# untitled.net
KiCad netlist of a schematic drawn in EAGLE
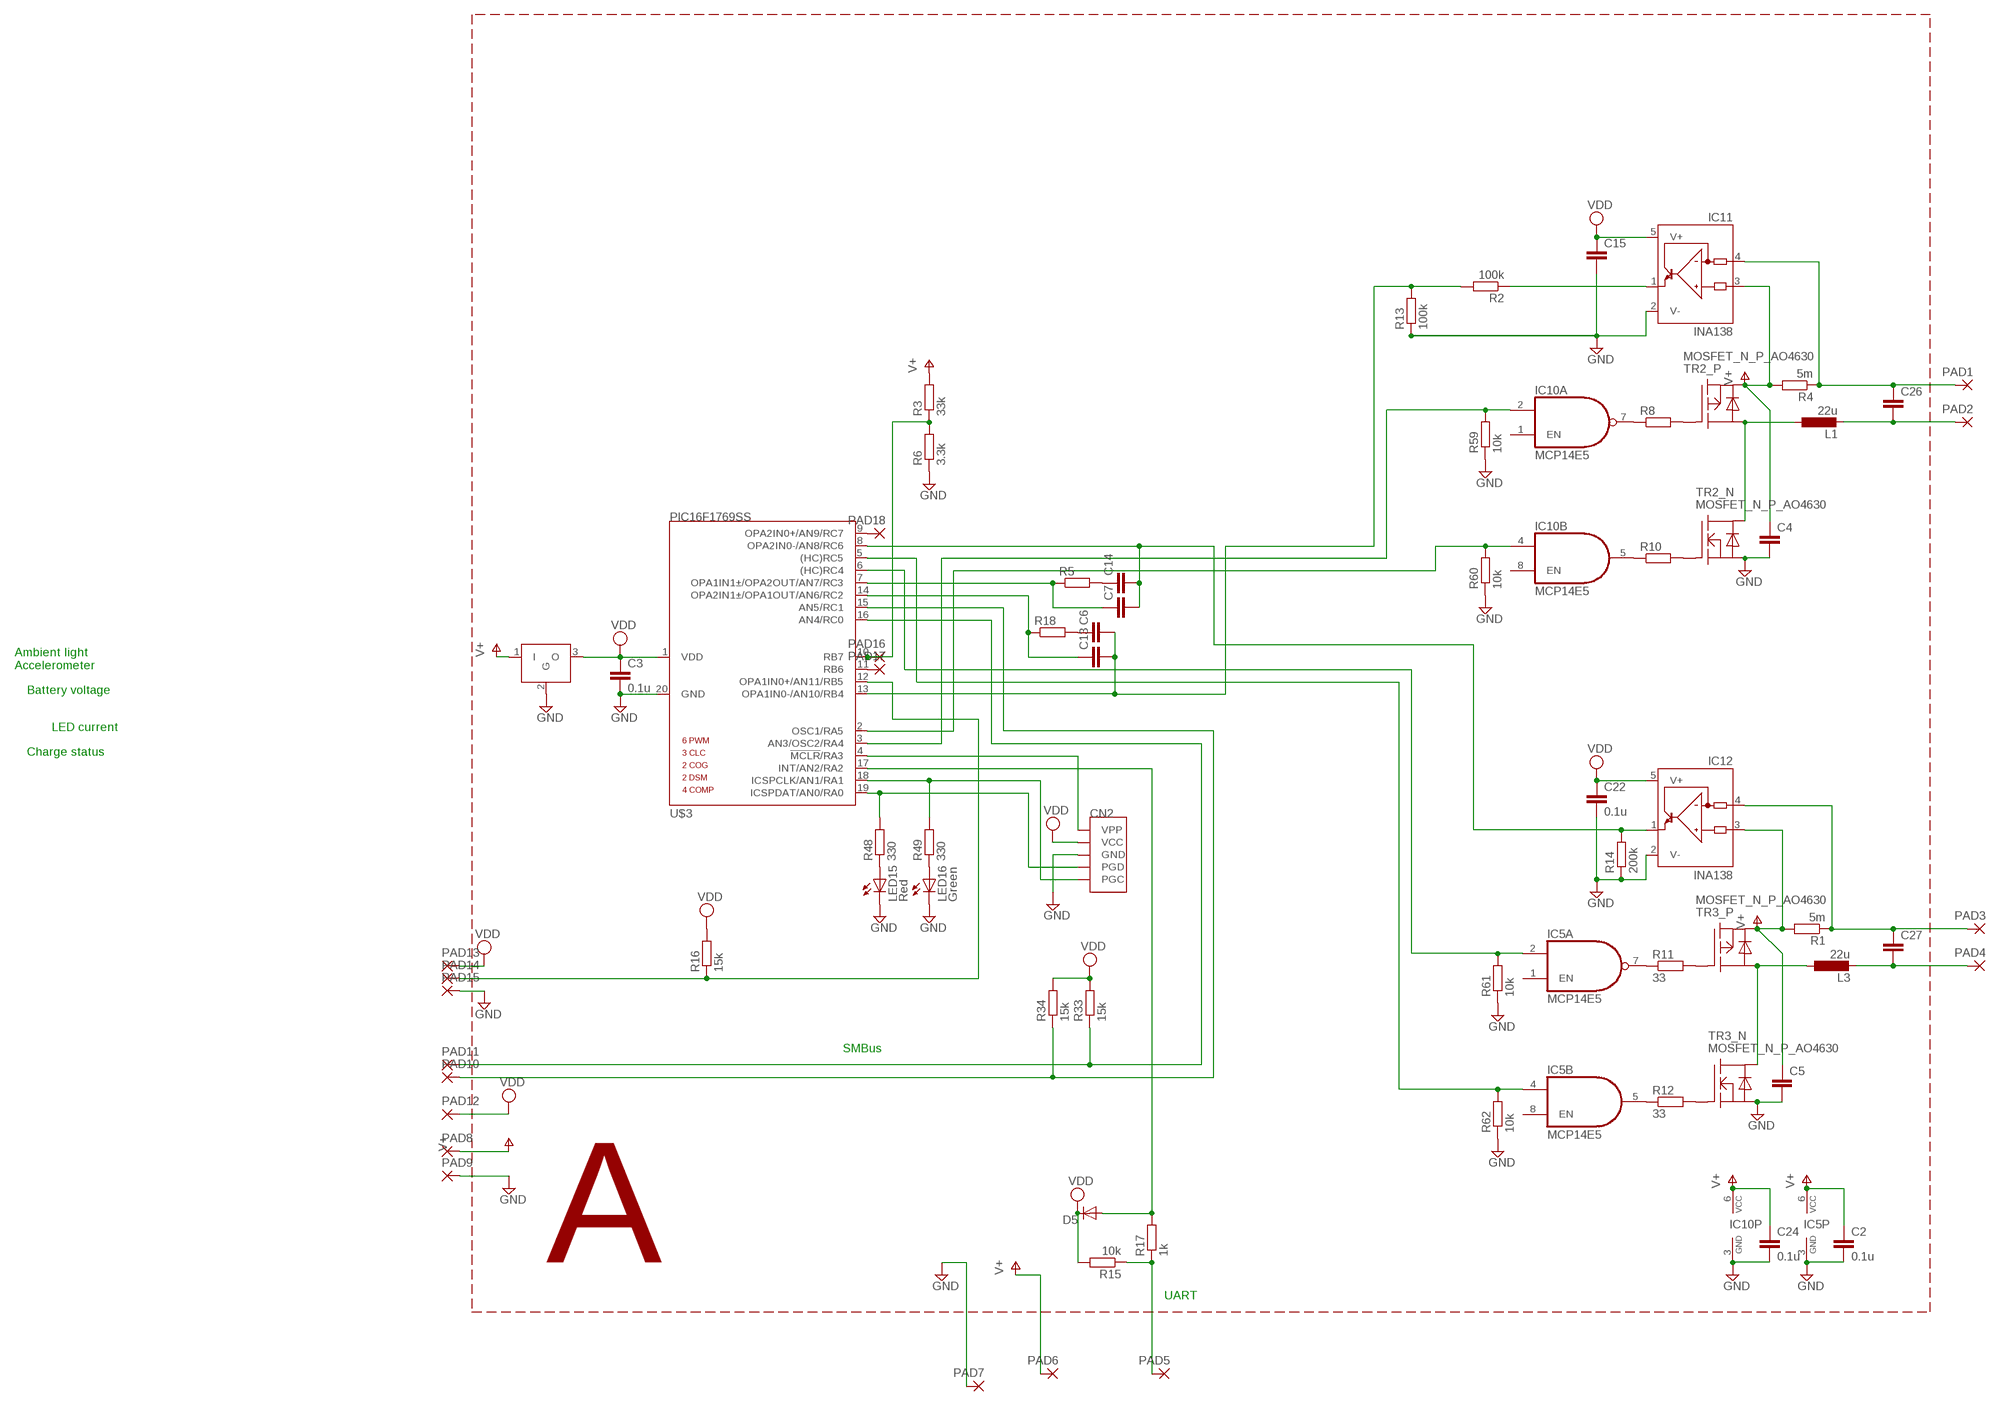
[diagram p0: schematic, sheet 1]

(export (version "E")
  (design (tool "Eeschema 10.0.6"))
  (components
    (comp (ref "C2")
      (value "0.1u")
      (footprint "eagle-import:C0402")
      (libsource (lib "eagle-import") (part "C-EUC0402"))
    )
    (comp (ref "C3")
      (value "0.1u")
      (footprint "eagle-import:C0402")
      (libsource (lib "eagle-import") (part "C-EUC0402"))
    )
    (comp (ref "C4")
      (value "C-EUC0805")
      (footprint "eagle-import:C0805")
      (libsource (lib "eagle-import") (part "C-EUC0805"))
    )
    (comp (ref "C5")
      (value "C-EUC0805")
      (footprint "eagle-import:C0805")
      (libsource (lib "eagle-import") (part "C-EUC0805"))
    )
    (comp (ref "C6")
      (value "C-EUC0402")
      (footprint "eagle-import:C0402")
      (libsource (lib "eagle-import") (part "C-EUC0402"))
    )
    (comp (ref "C7")
      (value "C-EUC0402")
      (footprint "eagle-import:C0402")
      (libsource (lib "eagle-import") (part "C-EUC0402"))
    )
    (comp (ref "C13")
      (value "C-EUC0402")
      (footprint "eagle-import:C0402")
      (libsource (lib "eagle-import") (part "C-EUC0402"))
    )
    (comp (ref "C14")
      (value "C-EUC0402")
      (footprint "eagle-import:C0402")
      (libsource (lib "eagle-import") (part "C-EUC0402"))
    )
    (comp (ref "C15")
      (value "C-EUC0402")
      (footprint "eagle-import:C0402")
      (libsource (lib "eagle-import") (part "C-EUC0402"))
    )
    (comp (ref "C22")
      (value "0.1u")
      (footprint "eagle-import:C0402")
      (libsource (lib "eagle-import") (part "C-EUC0402"))
    )
    (comp (ref "C24")
      (value "0.1u")
      (footprint "eagle-import:C0402")
      (libsource (lib "eagle-import") (part "C-EUC0402"))
    )
    (comp (ref "C26")
      (value "C-EUC0805")
      (footprint "eagle-import:C0805")
      (libsource (lib "eagle-import") (part "C-EUC0805"))
    )
    (comp (ref "C27")
      (value "C-EUC0805")
      (footprint "eagle-import:C0805")
      (libsource (lib "eagle-import") (part "C-EUC0805"))
    )
    (comp (ref "CN2")
      (value "ICSP")
      (footprint "eagle-import:MINI-ICSP")
      (libsource (lib "eagle-import") (part "ICSP"))
    )
    (comp (ref "D5")
      (value "DIODE-VMN2")
      (footprint "eagle-import:VMN2")
      (libsource (lib "eagle-import") (part "DIODE-VMN2"))
    )
    (comp (ref "IC5")
      (value "MCP14E5")
      (footprint "eagle-import:SO-08")
      (libsource (lib "eagle-import") (part "MCP14E5"))
    )
    (comp (ref "IC10")
      (value "MCP14E5")
      (footprint "eagle-import:SO-08")
      (libsource (lib "eagle-import") (part "MCP14E5"))
    )
    (comp (ref "IC11")
      (value "INA138")
      (footprint "eagle-import:SOT23-5")
      (fields (field (name "MF") "TEXAS INSTRUMENTS") (field (name "MPN") "INA138NA/250"))
      (libsource (lib "eagle-import") (part "INA138"))
    )
    (comp (ref "IC12")
      (value "INA138")
      (footprint "eagle-import:SOT23-5")
      (fields (field (name "MF") "TEXAS INSTRUMENTS") (field (name "MPN") "INA138NA/250"))
      (libsource (lib "eagle-import") (part "INA138"))
    )
    (comp (ref "L1")
      (value "22u")
      (footprint "eagle-import:SCRH125")
      (libsource (lib "eagle-import") (part "L-EUSCRH125"))
    )
    (comp (ref "L3")
      (value "22u")
      (footprint "eagle-import:SCRH125")
      (libsource (lib "eagle-import") (part "L-EUSCRH125"))
    )
    (comp (ref "LED15")
      (value "Red")
      (footprint "eagle-import:CHIP-LED1005")
      (libsource (lib "eagle-import") (part "LED1005"))
    )
    (comp (ref "LED16")
      (value "Green")
      (footprint "eagle-import:CHIP-LED1005")
      (libsource (lib "eagle-import") (part "LED1005"))
    )
    (comp (ref "PAD1")
      (value "1,6/0,8")
      (footprint "eagle-import:1,6_0,8")
      (libsource (lib "eagle-import") (part "1,6/0,8"))
    )
    (comp (ref "PAD2")
      (value "1,6/0,8")
      (footprint "eagle-import:1,6_0,8")
      (libsource (lib "eagle-import") (part "1,6/0,8"))
    )
    (comp (ref "PAD3")
      (value "1,6/0,8")
      (footprint "eagle-import:1,6_0,8")
      (libsource (lib "eagle-import") (part "1,6/0,8"))
    )
    (comp (ref "PAD4")
      (value "1,6/0,8")
      (footprint "eagle-import:1,6_0,8")
      (libsource (lib "eagle-import") (part "1,6/0,8"))
    )
    (comp (ref "PAD5")
      (value "1,6/0,8")
      (footprint "eagle-import:1,6_0,8")
      (libsource (lib "eagle-import") (part "1,6/0,8"))
    )
    (comp (ref "PAD6")
      (value "1,6/0,8")
      (footprint "eagle-import:1,6_0,8")
      (libsource (lib "eagle-import") (part "1,6/0,8"))
    )
    (comp (ref "PAD7")
      (value "1,6/0,8")
      (footprint "eagle-import:1,6_0,8")
      (libsource (lib "eagle-import") (part "1,6/0,8"))
    )
    (comp (ref "PAD8")
      (value "1,6/0,8")
      (footprint "eagle-import:1,6_0,8")
      (libsource (lib "eagle-import") (part "1,6/0,8"))
    )
    (comp (ref "PAD9")
      (value "1,6/0,8")
      (footprint "eagle-import:1,6_0,8")
      (libsource (lib "eagle-import") (part "1,6/0,8"))
    )
    (comp (ref "PAD10")
      (value "1,6/0,8")
      (footprint "eagle-import:1,6_0,8")
      (libsource (lib "eagle-import") (part "1,6/0,8"))
    )
    (comp (ref "PAD11")
      (value "1,6/0,8")
      (footprint "eagle-import:1,6_0,8")
      (libsource (lib "eagle-import") (part "1,6/0,8"))
    )
    (comp (ref "PAD12")
      (value "1,6/0,8")
      (footprint "eagle-import:1,6_0,8")
      (libsource (lib "eagle-import") (part "1,6/0,8"))
    )
    (comp (ref "PAD13")
      (value "1,6/0,8")
      (footprint "eagle-import:1,6_0,8")
      (libsource (lib "eagle-import") (part "1,6/0,8"))
    )
    (comp (ref "PAD14")
      (value "1,6/0,8")
      (footprint "eagle-import:1,6_0,8")
      (libsource (lib "eagle-import") (part "1,6/0,8"))
    )
    (comp (ref "PAD15")
      (value "1,6/0,8")
      (footprint "eagle-import:1,6_0,8")
      (libsource (lib "eagle-import") (part "1,6/0,8"))
    )
    (comp (ref "PAD16")
      (value "1,6/0,8")
      (footprint "eagle-import:1,6_0,8")
      (libsource (lib "eagle-import") (part "1,6/0,8"))
    )
    (comp (ref "PAD17")
      (value "1,6/0,8")
      (footprint "eagle-import:1,6_0,8")
      (libsource (lib "eagle-import") (part "1,6/0,8"))
    )
    (comp (ref "PAD18")
      (value "1,6/0,8")
      (footprint "eagle-import:1,6_0,8")
      (libsource (lib "eagle-import") (part "1,6/0,8"))
    )
    (comp (ref "R1")
      (value "5m")
      (footprint "eagle-import:R1210")
      (libsource (lib "eagle-import") (part "R-EU_R1210"))
    )
    (comp (ref "R2")
      (value "100k")
      (footprint "eagle-import:R0402")
      (libsource (lib "eagle-import") (part "R-EU_R0402"))
    )
    (comp (ref "R3")
      (value "33k")
      (footprint "eagle-import:R0402")
      (libsource (lib "eagle-import") (part "R-EU_R0402"))
    )
    (comp (ref "R4")
      (value "5m")
      (footprint "eagle-import:R1210")
      (libsource (lib "eagle-import") (part "R-EU_R1210"))
    )
    (comp (ref "R5")
      (value "R-EU_R0402")
      (footprint "eagle-import:R0402")
      (libsource (lib "eagle-import") (part "R-EU_R0402"))
    )
    (comp (ref "R6")
      (value "3.3k")
      (footprint "eagle-import:R0402")
      (libsource (lib "eagle-import") (part "R-EU_R0402"))
    )
    (comp (ref "R8")
      (value "R-EU_R0402")
      (footprint "eagle-import:R0402")
      (libsource (lib "eagle-import") (part "R-EU_R0402"))
    )
    (comp (ref "R10")
      (value "R-EU_R0402")
      (footprint "eagle-import:R0402")
      (libsource (lib "eagle-import") (part "R-EU_R0402"))
    )
    (comp (ref "R11")
      (value "33")
      (footprint "eagle-import:R0402")
      (libsource (lib "eagle-import") (part "R-EU_R0402"))
    )
    (comp (ref "R12")
      (value "33")
      (footprint "eagle-import:R0402")
      (libsource (lib "eagle-import") (part "R-EU_R0402"))
    )
    (comp (ref "R13")
      (value "100k")
      (footprint "eagle-import:R0402")
      (libsource (lib "eagle-import") (part "R-EU_R0402"))
    )
    (comp (ref "R14")
      (value "200k")
      (footprint "eagle-import:R0402")
      (libsource (lib "eagle-import") (part "R-EU_R0402"))
    )
    (comp (ref "R15")
      (value "10k")
      (footprint "eagle-import:R0402")
      (libsource (lib "eagle-import") (part "R-EU_R0402"))
    )
    (comp (ref "R16")
      (value "15k")
      (footprint "eagle-import:R0402")
      (libsource (lib "eagle-import") (part "R-EU_R0402"))
    )
    (comp (ref "R17")
      (value "1k")
      (footprint "eagle-import:R0402")
      (libsource (lib "eagle-import") (part "R-EU_R0402"))
    )
    (comp (ref "R18")
      (value "R-EU_R0402")
      (footprint "eagle-import:R0402")
      (libsource (lib "eagle-import") (part "R-EU_R0402"))
    )
    (comp (ref "R33")
      (value "15k")
      (footprint "eagle-import:R0402")
      (libsource (lib "eagle-import") (part "R-EU_R0402"))
    )
    (comp (ref "R34")
      (value "15k")
      (footprint "eagle-import:R0402")
      (libsource (lib "eagle-import") (part "R-EU_R0402"))
    )
    (comp (ref "R48")
      (value "330")
      (footprint "eagle-import:R0402")
      (libsource (lib "eagle-import") (part "R-EU_R0402"))
    )
    (comp (ref "R49")
      (value "330")
      (footprint "eagle-import:R0402")
      (libsource (lib "eagle-import") (part "R-EU_R0402"))
    )
    (comp (ref "R59")
      (value "10k")
      (footprint "eagle-import:R0402")
      (libsource (lib "eagle-import") (part "R-EU_R0402"))
    )
    (comp (ref "R60")
      (value "10k")
      (footprint "eagle-import:R0402")
      (libsource (lib "eagle-import") (part "R-EU_R0402"))
    )
    (comp (ref "R61")
      (value "10k")
      (footprint "eagle-import:R0402")
      (libsource (lib "eagle-import") (part "R-EU_R0402"))
    )
    (comp (ref "R62")
      (value "10k")
      (footprint "eagle-import:R0402")
      (libsource (lib "eagle-import") (part "R-EU_R0402"))
    )
    (comp (ref "TR2")
      (value "MOSFET_N_P_AO4630")
      (footprint "eagle-import:SO-08")
      (libsource (lib "eagle-import") (part "MOSFET_N_P_AO4630"))
    )
    (comp (ref "TR3")
      (value "MOSFET_N_P_AO4630")
      (footprint "eagle-import:SO-08")
      (libsource (lib "eagle-import") (part "MOSFET_N_P_AO4630"))
    )
    (comp (ref "U$2")
      (value "78-DC/DCV")
      (footprint "eagle-import:VXO78-500")
      (libsource (lib "eagle-import") (part "78-DC/DCV"))
    )
    (comp (ref "U$3")
      (value "PIC16F1769SS")
      (footprint "eagle-import:SSOP20")
      (libsource (lib "eagle-import") (part "PIC16F1769SS"))
    )
  )
  (nets
    (net (code "1") (name "GND") (class "Default")
      (node (ref "C15") (pin "2") (pinfunction "2_2") (pintype "passive"))
      (node (ref "C2") (pin "2") (pinfunction "2_2") (pintype "passive"))
      (node (ref "C22") (pin "2") (pinfunction "2_2") (pintype "passive"))
      (node (ref "C24") (pin "2") (pinfunction "2_2") (pintype "passive"))
      (node (ref "C3") (pin "2") (pinfunction "2_2") (pintype "passive"))
      (node (ref "C4") (pin "2") (pinfunction "2_2") (pintype "passive"))
      (node (ref "C5") (pin "2") (pinfunction "2_2") (pintype "passive"))
      (node (ref "CN2") (pin "GND") (pinfunction "GND_GND") (pintype "power_in"))
      (node (ref "IC10") (pin "3") (pinfunction "GND_3") (pintype "power_in"))
      (node (ref "IC11") (pin "2") (pinfunction "V-_2") (pintype "power_in"))
      (node (ref "IC12") (pin "2") (pinfunction "V-_2") (pintype "power_in"))
      (node (ref "IC5") (pin "3") (pinfunction "GND_3") (pintype "power_in"))
      (node (ref "LED15") (pin "C") (pinfunction "C_C") (pintype "passive"))
      (node (ref "LED16") (pin "C") (pinfunction "C_C") (pintype "passive"))
      (node (ref "PAD15") (pin "1") (pinfunction "P_1") (pintype "passive"))
      (node (ref "PAD7") (pin "1") (pinfunction "P_1") (pintype "passive"))
      (node (ref "PAD9") (pin "1") (pinfunction "P_1") (pintype "passive"))
      (node (ref "R13") (pin "1") (pinfunction "1_1") (pintype "passive"))
      (node (ref "R14") (pin "1") (pinfunction "1_1") (pintype "passive"))
      (node (ref "R59") (pin "1") (pinfunction "1_1") (pintype "passive"))
      (node (ref "R6") (pin "1") (pinfunction "1_1") (pintype "passive"))
      (node (ref "R60") (pin "1") (pinfunction "1_1") (pintype "passive"))
      (node (ref "R61") (pin "1") (pinfunction "1_1") (pintype "passive"))
      (node (ref "R62") (pin "1") (pinfunction "1_1") (pintype "passive"))
      (node (ref "TR2") (pin "1") (pinfunction "S_1") (pintype "bidirectional"))
      (node (ref "TR3") (pin "1") (pinfunction "S_1") (pintype "bidirectional"))
      (node (ref "U$2") (pin "2") (pinfunction "G_2") (pintype "input"))
      (node (ref "U$3") (pin "20") (pinfunction "GND_20") (pintype "power_in"))
    )
    (net (code "2") (name "Net-(C6-Pad1)") (class "Default")
      (node (ref "C6") (pin "1") (pinfunction "1_1") (pintype "passive"))
      (node (ref "R18") (pin "2") (pinfunction "2_2") (pintype "passive"))
    )
    (net (code "3") (name "Net-(C14-Pad1)") (class "Default")
      (node (ref "C14") (pin "1") (pinfunction "1_1") (pintype "passive"))
      (node (ref "R5") (pin "2") (pinfunction "2_2") (pintype "passive"))
    )
    (net (code "4") (name "Net-(IC5A-I)") (class "Default")
      (node (ref "IC5") (pin "2") (pinfunction "I_2") (pintype "input"))
      (node (ref "R61") (pin "2") (pinfunction "2_2") (pintype "passive"))
      (node (ref "U$3") (pin "6") (pinfunction "(HC)RC4_6") (pintype "bidirectional"))
    )
    (net (code "5") (name "Net-(IC5A-~{O})") (class "Default")
      (node (ref "IC5") (pin "7") (pinfunction "~{O}_7") (pintype "output"))
      (node (ref "R11") (pin "1") (pinfunction "1_1") (pintype "passive"))
    )
    (net (code "6") (name "Net-(IC5B-I)") (class "Default")
      (node (ref "IC5") (pin "4") (pinfunction "I_4") (pintype "input"))
      (node (ref "R62") (pin "2") (pinfunction "2_2") (pintype "passive"))
      (node (ref "U$3") (pin "5") (pinfunction "(HC)RC5_5") (pintype "bidirectional"))
    )
    (net (code "7") (name "Net-(IC5B-O)") (class "Default")
      (node (ref "IC5") (pin "5") (pinfunction "O_5") (pintype "output"))
      (node (ref "R12") (pin "1") (pinfunction "1_1") (pintype "passive"))
    )
    (net (code "8") (name "Net-(IC10A-I)") (class "Default")
      (node (ref "IC10") (pin "2") (pinfunction "I_2") (pintype "input"))
      (node (ref "R59") (pin "2") (pinfunction "2_2") (pintype "passive"))
      (node (ref "U$3") (pin "3") (pinfunction "AN3/OSC2/RA4_3") (pintype "bidirectional"))
    )
    (net (code "9") (name "Net-(IC10A-~{O})") (class "Default")
      (node (ref "IC10") (pin "7") (pinfunction "~{O}_7") (pintype "output"))
      (node (ref "R8") (pin "1") (pinfunction "1_1") (pintype "passive"))
    )
    (net (code "10") (name "Net-(IC10B-I)") (class "Default")
      (node (ref "IC10") (pin "4") (pinfunction "I_4") (pintype "input"))
      (node (ref "R60") (pin "2") (pinfunction "2_2") (pintype "passive"))
      (node (ref "U$3") (pin "2") (pinfunction "OSC1/RA5_2") (pintype "bidirectional"))
    )
    (net (code "11") (name "Net-(IC10B-O)") (class "Default")
      (node (ref "IC10") (pin "5") (pinfunction "O_5") (pintype "output"))
      (node (ref "R10") (pin "1") (pinfunction "1_1") (pintype "passive"))
    )
    (net (code "12") (name "Net-(IC11-IN-)") (class "Default")
      (node (ref "C26") (pin "1") (pinfunction "1_1") (pintype "passive"))
      (node (ref "IC11") (pin "4") (pinfunction "IN-_4") (pintype "input"))
      (node (ref "PAD1") (pin "1") (pinfunction "P_1") (pintype "passive"))
      (node (ref "R4") (pin "1") (pinfunction "1_1") (pintype "passive"))
    )
    (net (code "13") (name "Net-(IC11-OUT)") (class "Default")
      (node (ref "IC11") (pin "1") (pinfunction "OUT_1") (pintype "output"))
      (node (ref "R2") (pin "1") (pinfunction "1_1") (pintype "passive"))
    )
    (net (code "14") (name "Net-(IC12-IN-)") (class "Default")
      (node (ref "C27") (pin "1") (pinfunction "1_1") (pintype "passive"))
      (node (ref "IC12") (pin "4") (pinfunction "IN-_4") (pintype "input"))
      (node (ref "PAD3") (pin "1") (pinfunction "P_1") (pintype "passive"))
      (node (ref "R1") (pin "1") (pinfunction "1_1") (pintype "passive"))
    )
    (net (code "15") (name "Net-(IC12-OUT)") (class "Default")
      (node (ref "C14") (pin "2") (pinfunction "2_2") (pintype "passive"))
      (node (ref "C7") (pin "2") (pinfunction "2_2") (pintype "passive"))
      (node (ref "IC12") (pin "1") (pinfunction "OUT_1") (pintype "output"))
      (node (ref "R14") (pin "2") (pinfunction "2_2") (pintype "passive"))
      (node (ref "U$3") (pin "8") (pinfunction "OPA2IN0-/AN8/RC6_8") (pintype "bidirectional"))
    )
    (net (code "16") (name "Net-(L1-Pad1)") (class "Default")
      (node (ref "L1") (pin "1") (pinfunction "1_1") (pintype "passive"))
      (node (ref "TR2") (pin "5") (pinfunction "D_5") (pintype "bidirectional"))
      (node (ref "TR2") (pin "6") (pinfunction "D_6") (pintype "bidirectional"))
      (node (ref "TR2") (pin "7") (pinfunction "D_7") (pintype "bidirectional"))
      (node (ref "TR2") (pin "8") (pinfunction "D_8") (pintype "bidirectional"))
    )
    (net (code "17") (name "Net-(L3-Pad1)") (class "Default")
      (node (ref "L3") (pin "1") (pinfunction "1_1") (pintype "passive"))
      (node (ref "TR3") (pin "5") (pinfunction "D_5") (pintype "bidirectional"))
      (node (ref "TR3") (pin "6") (pinfunction "D_6") (pintype "bidirectional"))
      (node (ref "TR3") (pin "7") (pinfunction "D_7") (pintype "bidirectional"))
      (node (ref "TR3") (pin "8") (pinfunction "D_8") (pintype "bidirectional"))
    )
    (net (code "18") (name "Net-(LED15-PadA)") (class "Default")
      (node (ref "LED15") (pin "A") (pinfunction "A_A") (pintype "passive"))
      (node (ref "R48") (pin "1") (pinfunction "1_1") (pintype "passive"))
    )
    (net (code "19") (name "Net-(LED16-PadA)") (class "Default")
      (node (ref "LED16") (pin "A") (pinfunction "A_A") (pintype "passive"))
      (node (ref "R49") (pin "1") (pinfunction "1_1") (pintype "passive"))
    )
    (net (code "20") (name "Net-(PAD2-P)") (class "Default")
      (node (ref "C26") (pin "2") (pinfunction "2_2") (pintype "passive"))
      (node (ref "L1") (pin "2") (pinfunction "2_2") (pintype "passive"))
      (node (ref "PAD2") (pin "1") (pinfunction "P_1") (pintype "passive"))
    )
    (net (code "21") (name "Net-(PAD4-P)") (class "Default")
      (node (ref "C27") (pin "2") (pinfunction "2_2") (pintype "passive"))
      (node (ref "L3") (pin "2") (pinfunction "2_2") (pintype "passive"))
      (node (ref "PAD4") (pin "1") (pinfunction "P_1") (pintype "passive"))
    )
    (net (code "22") (name "Net-(PAD5-P)") (class "Default")
      (node (ref "PAD5") (pin "1") (pinfunction "P_1") (pintype "passive"))
      (node (ref "R15") (pin "1") (pinfunction "1_1") (pintype "passive"))
      (node (ref "R17") (pin "1") (pinfunction "1_1") (pintype "passive"))
    )
    (net (code "23") (name "Net-(PAD10-P)") (class "Default")
      (node (ref "PAD10") (pin "1") (pinfunction "P_1") (pintype "passive"))
      (node (ref "R34") (pin "1") (pinfunction "1_1") (pintype "passive"))
      (node (ref "U$3") (pin "15") (pinfunction "AN5/RC1_15") (pintype "bidirectional"))
    )
    (net (code "24") (name "Net-(PAD11-P)") (class "Default")
      (node (ref "PAD11") (pin "1") (pinfunction "P_1") (pintype "passive"))
      (node (ref "R33") (pin "1") (pinfunction "1_1") (pintype "passive"))
      (node (ref "U$3") (pin "16") (pinfunction "AN4/RC0_16") (pintype "bidirectional"))
    )
    (net (code "25") (name "Net-(PAD14-P)") (class "Default")
      (node (ref "PAD14") (pin "1") (pinfunction "P_1") (pintype "passive"))
      (node (ref "R16") (pin "1") (pinfunction "1_1") (pintype "passive"))
      (node (ref "U$3") (pin "12") (pinfunction "OPA1IN0+/AN11/RB5_12") (pintype "bidirectional"))
    )
    (net (code "26") (name "Net-(PAD16-P)") (class "Default")
      (node (ref "PAD16") (pin "1") (pinfunction "P_1") (pintype "passive"))
      (node (ref "R3") (pin "1") (pinfunction "1_1") (pintype "passive"))
      (node (ref "R6") (pin "2") (pinfunction "2_2") (pintype "passive"))
      (node (ref "U$3") (pin "10") (pinfunction "RB7_10") (pintype "bidirectional"))
    )
    (net (code "27") (name "Net-(PAD17-P)") (class "Default")
      (node (ref "PAD17") (pin "1") (pinfunction "P_1") (pintype "passive"))
      (node (ref "U$3") (pin "11") (pinfunction "RB6_11") (pintype "bidirectional"))
    )
    (net (code "28") (name "Net-(PAD18-P)") (class "Default")
      (node (ref "PAD18") (pin "1") (pinfunction "P_1") (pintype "passive"))
      (node (ref "U$3") (pin "9") (pinfunction "OPA2IN0+/AN9/RC7_9") (pintype "bidirectional"))
    )
    (net (code "29") (name "Net-(TR2A-G)") (class "Default")
      (node (ref "R10") (pin "2") (pinfunction "2_2") (pintype "passive"))
      (node (ref "TR2") (pin "2") (pinfunction "G_2") (pintype "bidirectional"))
    )
    (net (code "30") (name "Net-(TR2B-G)") (class "Default")
      (node (ref "R8") (pin "2") (pinfunction "2_2") (pintype "passive"))
      (node (ref "TR2") (pin "4") (pinfunction "G_4") (pintype "bidirectional"))
    )
    (net (code "31") (name "Net-(TR3A-G)") (class "Default")
      (node (ref "R12") (pin "2") (pinfunction "2_2") (pintype "passive"))
      (node (ref "TR3") (pin "2") (pinfunction "G_2") (pintype "bidirectional"))
    )
    (net (code "32") (name "Net-(TR3B-G)") (class "Default")
      (node (ref "R11") (pin "2") (pinfunction "2_2") (pintype "passive"))
      (node (ref "TR3") (pin "4") (pinfunction "G_4") (pintype "bidirectional"))
    )
    (net (code "33") (name "Net-(U$3-ICSPCLK{slash}AN1{slash}RA1)") (class "Default")
      (node (ref "CN2") (pin "PGC") (pinfunction "PGC_PGC") (pintype "output"))
      (node (ref "R49") (pin "2") (pinfunction "2_2") (pintype "passive"))
      (node (ref "U$3") (pin "18") (pinfunction "ICSPCLK/AN1/RA1_18") (pintype "bidirectional"))
    )
    (net (code "34") (name "Net-(U$3-ICSPDAT{slash}AN0{slash}RA0)") (class "Default")
      (node (ref "CN2") (pin "PGD") (pinfunction "PGD_PGD") (pintype "bidirectional"))
      (node (ref "R48") (pin "2") (pinfunction "2_2") (pintype "passive"))
      (node (ref "U$3") (pin "19") (pinfunction "ICSPDAT/AN0/RA0_19") (pintype "bidirectional"))
    )
    (net (code "35") (name "Net-(U$3-INT{slash}AN2{slash}RA2)") (class "Default")
      (node (ref "D5") (pin "A") (pinfunction "A_A") (pintype "passive"))
      (node (ref "R17") (pin "2") (pinfunction "2_2") (pintype "passive"))
      (node (ref "U$3") (pin "17") (pinfunction "INT/AN2/RA2_17") (pintype "bidirectional"))
    )
    (net (code "36") (name "Net-(U$3-OPA1IN0-{slash}AN10{slash}RB4)") (class "Default")
      (node (ref "C13") (pin "2") (pinfunction "2_2") (pintype "passive"))
      (node (ref "C6") (pin "2") (pinfunction "2_2") (pintype "passive"))
      (node (ref "R13") (pin "2") (pinfunction "2_2") (pintype "passive"))
      (node (ref "R2") (pin "2") (pinfunction "2_2") (pintype "passive"))
      (node (ref "U$3") (pin "13") (pinfunction "OPA1IN0-/AN10/RB4_13") (pintype "bidirectional"))
    )
    (net (code "37") (name "Net-(U$3-OPA1IN1±{slash}OPA2OUT{slash}AN7{slash}RC3)") (class "Default")
      (node (ref "C7") (pin "1") (pinfunction "1_1") (pintype "passive"))
      (node (ref "R5") (pin "1") (pinfunction "1_1") (pintype "passive"))
      (node (ref "U$3") (pin "7") (pinfunction "OPA1IN1±/OPA2OUT/AN7/RC3_7") (pintype "bidirectional"))
    )
    (net (code "38") (name "Net-(U$3-OPA2IN1±{slash}OPA1OUT{slash}AN6{slash}RC2)") (class "Default")
      (node (ref "C13") (pin "1") (pinfunction "1_1") (pintype "passive"))
      (node (ref "R18") (pin "1") (pinfunction "1_1") (pintype "passive"))
      (node (ref "U$3") (pin "14") (pinfunction "OPA2IN1±/OPA1OUT/AN6/RC2_14") (pintype "bidirectional"))
    )
    (net (code "39") (name "Net-(U$3-~{MCLR}{slash}RA3)") (class "Default")
      (node (ref "CN2") (pin "VPP") (pinfunction "VPP_VPP") (pintype "output"))
      (node (ref "U$3") (pin "4") (pinfunction "~{MCLR}/RA3_4") (pintype "input"))
    )
    (net (code "40") (name "V+") (class "Default")
      (node (ref "C2") (pin "1") (pinfunction "1_1") (pintype "passive"))
      (node (ref "C24") (pin "1") (pinfunction "1_1") (pintype "passive"))
      (node (ref "C4") (pin "1") (pinfunction "1_1") (pintype "passive"))
      (node (ref "C5") (pin "1") (pinfunction "1_1") (pintype "passive"))
      (node (ref "IC10") (pin "6") (pinfunction "VCC_6") (pintype "power_in"))
      (node (ref "IC11") (pin "3") (pinfunction "IN+_3") (pintype "input"))
      (node (ref "IC12") (pin "3") (pinfunction "IN+_3") (pintype "input"))
      (node (ref "IC5") (pin "6") (pinfunction "VCC_6") (pintype "power_in"))
      (node (ref "PAD6") (pin "1") (pinfunction "P_1") (pintype "passive"))
      (node (ref "PAD8") (pin "1") (pinfunction "P_1") (pintype "passive"))
      (node (ref "R1") (pin "2") (pinfunction "2_2") (pintype "passive"))
      (node (ref "R3") (pin "2") (pinfunction "2_2") (pintype "passive"))
      (node (ref "R4") (pin "2") (pinfunction "2_2") (pintype "passive"))
      (node (ref "TR2") (pin "3") (pinfunction "S_3") (pintype "bidirectional"))
      (node (ref "TR3") (pin "3") (pinfunction "S_3") (pintype "bidirectional"))
      (node (ref "U$2") (pin "1") (pinfunction "I_1") (pintype "input"))
    )
    (net (code "41") (name "VDD") (class "Default")
      (node (ref "C15") (pin "1") (pinfunction "1_1") (pintype "passive"))
      (node (ref "C22") (pin "1") (pinfunction "1_1") (pintype "passive"))
      (node (ref "C3") (pin "1") (pinfunction "1_1") (pintype "passive"))
      (node (ref "CN2") (pin "VCC") (pinfunction "VCC_VCC") (pintype "power_in"))
      (node (ref "D5") (pin "C") (pinfunction "C_C") (pintype "passive"))
      (node (ref "IC11") (pin "5") (pinfunction "V+_5") (pintype "power_in"))
      (node (ref "IC12") (pin "5") (pinfunction "V+_5") (pintype "power_in"))
      (node (ref "PAD12") (pin "1") (pinfunction "P_1") (pintype "passive"))
      (node (ref "PAD13") (pin "1") (pinfunction "P_1") (pintype "passive"))
      (node (ref "R15") (pin "2") (pinfunction "2_2") (pintype "passive"))
      (node (ref "R16") (pin "2") (pinfunction "2_2") (pintype "passive"))
      (node (ref "R33") (pin "2") (pinfunction "2_2") (pintype "passive"))
      (node (ref "R34") (pin "2") (pinfunction "2_2") (pintype "passive"))
      (node (ref "U$2") (pin "3") (pinfunction "O_3") (pintype "passive"))
      (node (ref "U$3") (pin "1") (pinfunction "VDD_1") (pintype "power_in"))
    )
    (net (code "42") (name "unconnected-(IC5A-EN-Pad1)") (class "Default")
      (node (ref "IC5") (pin "1") (pinfunction "EN_1") (pintype "input"))
    )
    (net (code "43") (name "unconnected-(IC5B-EN-Pad8)") (class "Default")
      (node (ref "IC5") (pin "8") (pinfunction "EN_8") (pintype "input"))
    )
    (net (code "44") (name "unconnected-(IC10A-EN-Pad1)") (class "Default")
      (node (ref "IC10") (pin "1") (pinfunction "EN_1") (pintype "input"))
    )
    (net (code "45") (name "unconnected-(IC10B-EN-Pad8)") (class "Default")
      (node (ref "IC10") (pin "8") (pinfunction "EN_8") (pintype "input"))
    )
  )
)
